# circuitdraft.net
KiCad netlist of a schematic drawn in EAGLE
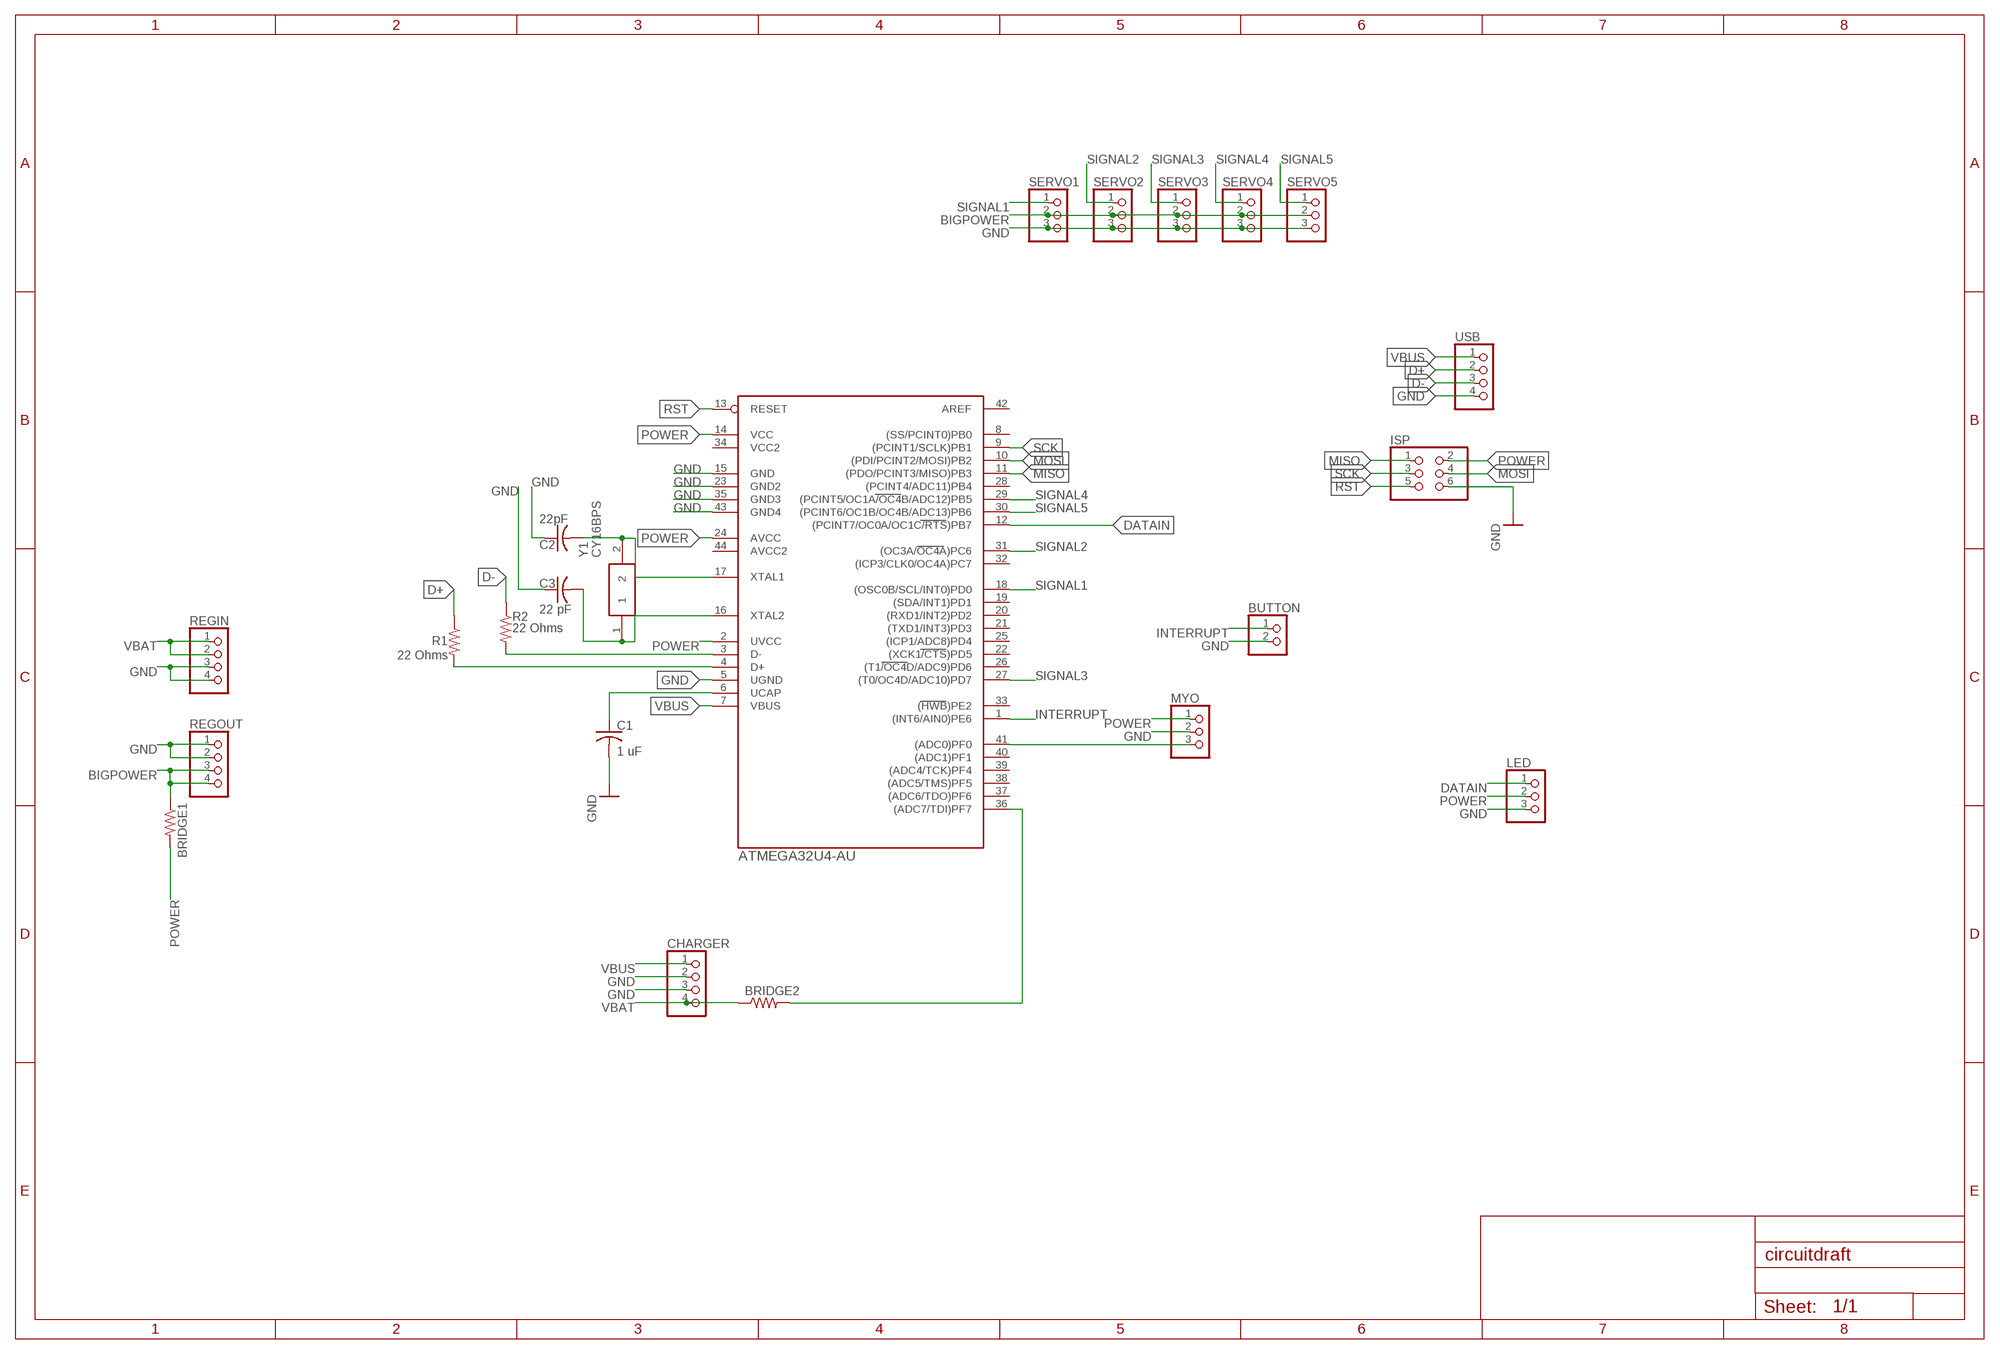
[diagram p0: schematic, sheet 1]

(export (version "E")
  (design (tool "Eeschema 10.0.6"))
  (components
    (comp (ref "BRIDGE1")
      (value "R-US_M0805")
      (footprint "eagle-import:M0805")
      (libsource (lib "eagle-import") (part "R-US_M0805"))
    )
    (comp (ref "BRIDGE2")
      (value "R-US_M0805")
      (footprint "eagle-import:M0805")
      (libsource (lib "eagle-import") (part "R-US_M0805"))
    )
    (comp (ref "BUTTON")
      (value "PINHD-1X2")
      (footprint "eagle-import:1X02")
      (libsource (lib "eagle-import") (part "PINHD-1X2"))
    )
    (comp (ref "C1")
      (value "1 uF")
      (footprint "eagle-import:C050-024X044")
      (libsource (lib "eagle-import") (part "C-US050-024X044"))
    )
    (comp (ref "C2")
      (value "22pF")
      (footprint "eagle-import:C025-024X044")
      (libsource (lib "eagle-import") (part "C-US025-024X044"))
    )
    (comp (ref "C3")
      (value "22 pF")
      (footprint "eagle-import:C025-024X044")
      (libsource (lib "eagle-import") (part "C-US025-024X044"))
    )
    (comp (ref "CHARGER")
      (value "PINHD-1X4")
      (footprint "eagle-import:1X04")
      (libsource (lib "eagle-import") (part "PINHD-1X4"))
    )
    (comp (ref "ISP")
      (value "PINHD-2X3")
      (footprint "eagle-import:2X03")
      (libsource (lib "eagle-import") (part "PINHD-2X3"))
    )
    (comp (ref "LED")
      (value "PINHD-1X3")
      (footprint "eagle-import:1X03")
      (libsource (lib "eagle-import") (part "PINHD-1X3"))
    )
    (comp (ref "MYO")
      (value "PINHD-1X3")
      (footprint "eagle-import:1X03")
      (libsource (lib "eagle-import") (part "PINHD-1X3"))
    )
    (comp (ref "R1")
      (value "22 Ohms")
      (footprint "eagle-import:0207_10")
      (libsource (lib "eagle-import") (part "R-US_0207/10"))
    )
    (comp (ref "R2")
      (value "22 Ohms")
      (footprint "eagle-import:0207_10")
      (libsource (lib "eagle-import") (part "R-US_0207/10"))
    )
    (comp (ref "REGIN")
      (value "PINHD-1X4")
      (footprint "eagle-import:1X04")
      (libsource (lib "eagle-import") (part "PINHD-1X4"))
    )
    (comp (ref "REGOUT")
      (value "PINHD-1X4")
      (footprint "eagle-import:1X04")
      (libsource (lib "eagle-import") (part "PINHD-1X4"))
    )
    (comp (ref "SERVO1")
      (value "PINHD-1X3")
      (footprint "eagle-import:1X03")
      (libsource (lib "eagle-import") (part "PINHD-1X3"))
    )
    (comp (ref "SERVO2")
      (value "PINHD-1X3")
      (footprint "eagle-import:1X03")
      (libsource (lib "eagle-import") (part "PINHD-1X3"))
    )
    (comp (ref "SERVO3")
      (value "PINHD-1X3")
      (footprint "eagle-import:1X03")
      (libsource (lib "eagle-import") (part "PINHD-1X3"))
    )
    (comp (ref "SERVO4")
      (value "PINHD-1X3")
      (footprint "eagle-import:1X03")
      (libsource (lib "eagle-import") (part "PINHD-1X3"))
    )
    (comp (ref "SERVO5")
      (value "PINHD-1X3")
      (footprint "eagle-import:1X03")
      (libsource (lib "eagle-import") (part "PINHD-1X3"))
    )
    (comp (ref "U$1")
      (value "ATMEGA32U4-AU")
      (footprint "eagle-import:TQFP44")
      (libsource (lib "eagle-import") (part "ATMEGA32U4-AU"))
    )
    (comp (ref "USB")
      (value "PINHD-1X4")
      (footprint "eagle-import:1X04")
      (libsource (lib "eagle-import") (part "PINHD-1X4"))
    )
    (comp (ref "Y1")
      (value "CY16BPS")
      (footprint "eagle-import:CY16BPS")
      (fields (field (name "MOUSER_PART_NUMBER") "549-CY16BPS"))
      (libsource (lib "eagle-import") (part "CY16BPS"))
    )
  )
  (nets
    (net (code "1") (name "/BIGPOWER") (class "Default")
      (node (ref "BRIDGE1") (pin "1") (pinfunction "1_1") (pintype "passive"))
      (node (ref "REGOUT") (pin "3") (pinfunction "3_3") (pintype "passive"))
      (node (ref "REGOUT") (pin "4") (pinfunction "4_4") (pintype "passive"))
      (node (ref "SERVO1") (pin "2") (pinfunction "2_2") (pintype "passive"))
      (node (ref "SERVO2") (pin "2") (pinfunction "2_2") (pintype "passive"))
      (node (ref "SERVO3") (pin "2") (pinfunction "2_2") (pintype "passive"))
      (node (ref "SERVO4") (pin "2") (pinfunction "2_2") (pintype "passive"))
      (node (ref "SERVO5") (pin "2") (pinfunction "2_2") (pintype "passive"))
    )
    (net (code "2") (name "/INTERRUPT") (class "Default")
      (node (ref "BUTTON") (pin "1") (pinfunction "1_1") (pintype "passive"))
      (node (ref "U$1") (pin "1") (pinfunction "(INT6/AIN0)PE6_1") (pintype "bidirectional"))
    )
    (net (code "3") (name "/SIGNAL1") (class "Default")
      (node (ref "SERVO1") (pin "1") (pinfunction "1_1") (pintype "passive"))
      (node (ref "U$1") (pin "18") (pinfunction "(OSC0B/SCL/INT0)PD0_18") (pintype "bidirectional"))
    )
    (net (code "4") (name "/SIGNAL2") (class "Default")
      (node (ref "SERVO2") (pin "1") (pinfunction "1_1") (pintype "passive"))
      (node (ref "U$1") (pin "31") (pinfunction "(OC3A/OC4A)PC6_31") (pintype "bidirectional"))
    )
    (net (code "5") (name "/SIGNAL3") (class "Default")
      (node (ref "SERVO3") (pin "1") (pinfunction "1_1") (pintype "passive"))
      (node (ref "U$1") (pin "27") (pinfunction "(T0/OC4D/ADC10)PD7_27") (pintype "bidirectional"))
    )
    (net (code "6") (name "/SIGNAL4") (class "Default")
      (node (ref "SERVO4") (pin "1") (pinfunction "1_1") (pintype "passive"))
      (node (ref "U$1") (pin "29") (pinfunction "(PCINT5/OC1A/OC4B/ADC12)PB5_29") (pintype "bidirectional"))
    )
    (net (code "7") (name "/SIGNAL5") (class "Default")
      (node (ref "SERVO5") (pin "1") (pinfunction "1_1") (pintype "passive"))
      (node (ref "U$1") (pin "30") (pinfunction "(PCINT6/OC1B/OC4B/ADC13)PB6_30") (pintype "bidirectional"))
    )
    (net (code "8") (name "/VBAT") (class "Default")
      (node (ref "BRIDGE2") (pin "1") (pinfunction "1_1") (pintype "passive"))
      (node (ref "CHARGER") (pin "4") (pinfunction "4_4") (pintype "passive"))
      (node (ref "REGIN") (pin "1") (pinfunction "1_1") (pintype "passive"))
      (node (ref "REGIN") (pin "2") (pinfunction "2_2") (pintype "passive"))
    )
    (net (code "9") (name "D+") (class "Default")
      (node (ref "R1") (pin "1") (pinfunction "1_1") (pintype "passive"))
      (node (ref "USB") (pin "2") (pinfunction "2_2") (pintype "passive"))
    )
    (net (code "10") (name "D-") (class "Default")
      (node (ref "R2") (pin "1") (pinfunction "1_1") (pintype "passive"))
      (node (ref "USB") (pin "3") (pinfunction "3_3") (pintype "passive"))
    )
    (net (code "11") (name "DATAIN") (class "Default")
      (node (ref "LED") (pin "1") (pinfunction "1_1") (pintype "passive"))
      (node (ref "U$1") (pin "12") (pinfunction "(PCINT7/OC0A/OC1C/RTS)PB7_12") (pintype "bidirectional"))
    )
    (net (code "12") (name "GND") (class "Default")
      (node (ref "BUTTON") (pin "2") (pinfunction "2_2") (pintype "passive"))
      (node (ref "C1") (pin "2") (pinfunction "2_2") (pintype "passive"))
      (node (ref "C2") (pin "1") (pinfunction "1_1") (pintype "passive"))
      (node (ref "C3") (pin "1") (pinfunction "1_1") (pintype "passive"))
      (node (ref "CHARGER") (pin "2") (pinfunction "2_2") (pintype "passive"))
      (node (ref "CHARGER") (pin "3") (pinfunction "3_3") (pintype "passive"))
      (node (ref "ISP") (pin "6") (pinfunction "6_6") (pintype "passive"))
      (node (ref "LED") (pin "3") (pinfunction "3_3") (pintype "passive"))
      (node (ref "MYO") (pin "2") (pinfunction "2_2") (pintype "passive"))
      (node (ref "REGIN") (pin "3") (pinfunction "3_3") (pintype "passive"))
      (node (ref "REGIN") (pin "4") (pinfunction "4_4") (pintype "passive"))
      (node (ref "REGOUT") (pin "1") (pinfunction "1_1") (pintype "passive"))
      (node (ref "REGOUT") (pin "2") (pinfunction "2_2") (pintype "passive"))
      (node (ref "SERVO1") (pin "3") (pinfunction "3_3") (pintype "passive"))
      (node (ref "SERVO2") (pin "3") (pinfunction "3_3") (pintype "passive"))
      (node (ref "SERVO3") (pin "3") (pinfunction "3_3") (pintype "passive"))
      (node (ref "SERVO4") (pin "3") (pinfunction "3_3") (pintype "passive"))
      (node (ref "SERVO5") (pin "3") (pinfunction "3_3") (pintype "passive"))
      (node (ref "U$1") (pin "15") (pinfunction "GND_15") (pintype "bidirectional"))
      (node (ref "U$1") (pin "23") (pinfunction "GND2_23") (pintype "bidirectional"))
      (node (ref "U$1") (pin "35") (pinfunction "GND3_35") (pintype "bidirectional"))
      (node (ref "U$1") (pin "43") (pinfunction "GND4_43") (pintype "bidirectional"))
      (node (ref "U$1") (pin "5") (pinfunction "UGND_5") (pintype "bidirectional"))
      (node (ref "USB") (pin "4") (pinfunction "4_4") (pintype "passive"))
    )
    (net (code "13") (name "MISO") (class "Default")
      (node (ref "ISP") (pin "1") (pinfunction "1_1") (pintype "passive"))
      (node (ref "U$1") (pin "11") (pinfunction "(PDO/PCINT3/MISO)PB3_11") (pintype "bidirectional"))
    )
    (net (code "14") (name "MOSI") (class "Default")
      (node (ref "ISP") (pin "4") (pinfunction "4_4") (pintype "passive"))
      (node (ref "U$1") (pin "10") (pinfunction "(PDI/PCINT2/MOSI)PB2_10") (pintype "bidirectional"))
    )
    (net (code "15") (name "Net-(U$1-(ADC0)PF0)") (class "Default")
      (node (ref "MYO") (pin "3") (pinfunction "3_3") (pintype "passive"))
      (node (ref "U$1") (pin "41") (pinfunction "(ADC0)PF0_41") (pintype "bidirectional"))
    )
    (net (code "16") (name "Net-(U$1-(ADC7{slash}TDI)PF7)") (class "Default")
      (node (ref "BRIDGE2") (pin "2") (pinfunction "2_2") (pintype "passive"))
      (node (ref "U$1") (pin "36") (pinfunction "(ADC7/TDI)PF7_36") (pintype "bidirectional"))
    )
    (net (code "17") (name "Net-(U$1-D+)") (class "Default")
      (node (ref "R1") (pin "2") (pinfunction "2_2") (pintype "passive"))
      (node (ref "U$1") (pin "4") (pinfunction "D+_4") (pintype "bidirectional"))
    )
    (net (code "18") (name "Net-(U$1-D-)") (class "Default")
      (node (ref "R2") (pin "2") (pinfunction "2_2") (pintype "passive"))
      (node (ref "U$1") (pin "3") (pinfunction "D-_3") (pintype "bidirectional"))
    )
    (net (code "19") (name "Net-(U$1-UCAP)") (class "Default")
      (node (ref "C1") (pin "1") (pinfunction "1_1") (pintype "passive"))
      (node (ref "U$1") (pin "6") (pinfunction "UCAP_6") (pintype "bidirectional"))
    )
    (net (code "20") (name "Net-(U$1-XTAL1)") (class "Default")
      (node (ref "C2") (pin "2") (pinfunction "2_2") (pintype "passive"))
      (node (ref "U$1") (pin "17") (pinfunction "XTAL1_17") (pintype "bidirectional"))
      (node (ref "Y1") (pin "2") (pinfunction "2_2") (pintype "bidirectional"))
    )
    (net (code "21") (name "Net-(U$1-XTAL2)") (class "Default")
      (node (ref "C3") (pin "2") (pinfunction "2_2") (pintype "passive"))
      (node (ref "U$1") (pin "16") (pinfunction "XTAL2_16") (pintype "bidirectional"))
      (node (ref "Y1") (pin "1") (pinfunction "1_1") (pintype "bidirectional"))
    )
    (net (code "22") (name "POWER") (class "Default")
      (node (ref "BRIDGE1") (pin "2") (pinfunction "2_2") (pintype "passive"))
      (node (ref "ISP") (pin "2") (pinfunction "2_2") (pintype "passive"))
      (node (ref "LED") (pin "2") (pinfunction "2_2") (pintype "passive"))
      (node (ref "MYO") (pin "1") (pinfunction "1_1") (pintype "passive"))
      (node (ref "U$1") (pin "14") (pinfunction "VCC_14") (pintype "bidirectional"))
      (node (ref "U$1") (pin "2") (pinfunction "UVCC_2") (pintype "bidirectional"))
      (node (ref "U$1") (pin "24") (pinfunction "AVCC_24") (pintype "bidirectional"))
    )
    (net (code "23") (name "RST") (class "Default")
      (node (ref "ISP") (pin "5") (pinfunction "5_5") (pintype "passive"))
      (node (ref "U$1") (pin "13") (pinfunction "RESET_13") (pintype "bidirectional"))
    )
    (net (code "24") (name "SCK") (class "Default")
      (node (ref "ISP") (pin "3") (pinfunction "3_3") (pintype "passive"))
      (node (ref "U$1") (pin "9") (pinfunction "(PCINT1/SCLK)PB1_9") (pintype "bidirectional"))
    )
    (net (code "25") (name "VBUS") (class "Default")
      (node (ref "CHARGER") (pin "1") (pinfunction "1_1") (pintype "passive"))
      (node (ref "U$1") (pin "7") (pinfunction "VBUS_7") (pintype "bidirectional"))
      (node (ref "USB") (pin "1") (pinfunction "1_1") (pintype "passive"))
    )
    (net (code "26") (name "unconnected-(U$1-(ADC1)PF1-Pad40)") (class "Default")
      (node (ref "U$1") (pin "40") (pinfunction "(ADC1)PF1_40") (pintype "bidirectional"))
    )
    (net (code "27") (name "unconnected-(U$1-(ADC4{slash}TCK)PF4-Pad39)") (class "Default")
      (node (ref "U$1") (pin "39") (pinfunction "(ADC4/TCK)PF4_39") (pintype "bidirectional"))
    )
    (net (code "28") (name "unconnected-(U$1-(ADC5{slash}TMS)PF5-Pad38)") (class "Default")
      (node (ref "U$1") (pin "38") (pinfunction "(ADC5/TMS)PF5_38") (pintype "bidirectional"))
    )
    (net (code "29") (name "unconnected-(U$1-(ADC6{slash}TDO)PF6-Pad37)") (class "Default")
      (node (ref "U$1") (pin "37") (pinfunction "(ADC6/TDO)PF6_37") (pintype "bidirectional"))
    )
    (net (code "30") (name "unconnected-(U$1-(HWB)PE2-Pad33)") (class "Default")
      (node (ref "U$1") (pin "33") (pinfunction "(HWB)PE2_33") (pintype "bidirectional"))
    )
    (net (code "31") (name "unconnected-(U$1-(ICP1{slash}ADC8)PD4-Pad25)") (class "Default")
      (node (ref "U$1") (pin "25") (pinfunction "(ICP1/ADC8)PD4_25") (pintype "bidirectional"))
    )
    (net (code "32") (name "unconnected-(U$1-(ICP3{slash}CLK0{slash}OC4A)PC7-Pad32)") (class "Default")
      (node (ref "U$1") (pin "32") (pinfunction "(ICP3/CLK0/OC4A)PC7_32") (pintype "bidirectional"))
    )
    (net (code "33") (name "unconnected-(U$1-(PCINT4{slash}ADC11)PB4-Pad28)") (class "Default")
      (node (ref "U$1") (pin "28") (pinfunction "(PCINT4/ADC11)PB4_28") (pintype "bidirectional"))
    )
    (net (code "34") (name "unconnected-(U$1-(RXD1{slash}INT2)PD2-Pad20)") (class "Default")
      (node (ref "U$1") (pin "20") (pinfunction "(RXD1/INT2)PD2_20") (pintype "bidirectional"))
    )
    (net (code "35") (name "unconnected-(U$1-(SDA{slash}INT1)PD1-Pad19)") (class "Default")
      (node (ref "U$1") (pin "19") (pinfunction "(SDA/INT1)PD1_19") (pintype "bidirectional"))
    )
    (net (code "36") (name "unconnected-(U$1-(SS{slash}PCINT0)PB0-Pad8)") (class "Default")
      (node (ref "U$1") (pin "8") (pinfunction "(SS/PCINT0)PB0_8") (pintype "bidirectional"))
    )
    (net (code "37") (name "unconnected-(U$1-(T1{slash}OC4D{slash}ADC9)PD6-Pad26)") (class "Default")
      (node (ref "U$1") (pin "26") (pinfunction "(T1/OC4D/ADC9)PD6_26") (pintype "bidirectional"))
    )
    (net (code "38") (name "unconnected-(U$1-(TXD1{slash}INT3)PD3-Pad21)") (class "Default")
      (node (ref "U$1") (pin "21") (pinfunction "(TXD1/INT3)PD3_21") (pintype "bidirectional"))
    )
    (net (code "39") (name "unconnected-(U$1-(XCK1{slash}CTS)PD5-Pad22)") (class "Default")
      (node (ref "U$1") (pin "22") (pinfunction "(XCK1/CTS)PD5_22") (pintype "bidirectional"))
    )
    (net (code "40") (name "unconnected-(U$1-AREF-Pad42)") (class "Default")
      (node (ref "U$1") (pin "42") (pinfunction "AREF_42") (pintype "bidirectional"))
    )
    (net (code "41") (name "unconnected-(U$1-AVCC2-Pad44)") (class "Default")
      (node (ref "U$1") (pin "44") (pinfunction "AVCC2_44") (pintype "bidirectional"))
    )
    (net (code "42") (name "unconnected-(U$1-VCC2-Pad34)") (class "Default")
      (node (ref "U$1") (pin "34") (pinfunction "VCC2_34") (pintype "bidirectional"))
    )
  )
)
